# Display.net
KiCad netlist of a schematic drawn in Altium Designer
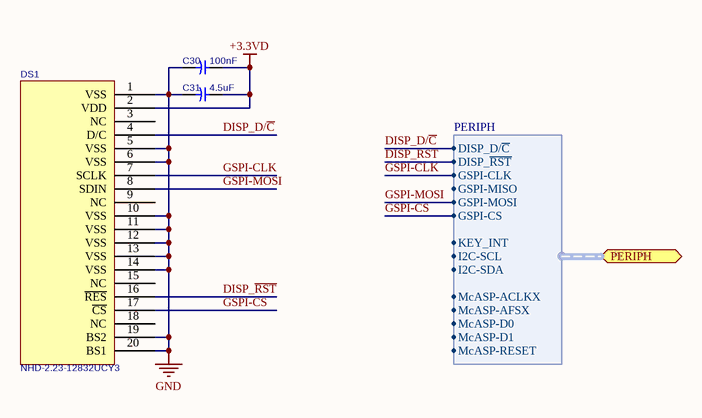
[diagram p0: Display.SchDoc]

(export (version "E")
  (design (tool "Eeschema 10.0.6"))
  (components
    (comp (ref "C30") (value "100nF") (footprint "C_0603A") (libsource (lib "WiFi_3200") (part "C_0603")))
    (comp (ref "C31") (value "4.5uF") (footprint "C_0603A") (libsource (lib "WiFi_3200") (part "C_0603")))
    (comp (ref "DS1")
      (value "NHD-2.23-12832UCY3")
      (footprint "NHD-2.23-12832UCY3_FP")
      (description "OLED DISPLAY")
      (fields (field (name "MANUFACTURER") "Newhaven Display Intl"))
      (libsource (lib "WiFi_3200") (part "NHD-2.23-12832UCY3"))
    )
  )
  (nets
    (net (code "2") (name "+3.3VD") (class "Default")
      (node (ref "C30") (pin "1") (pinfunction "1_1") (pintype "passive"))
      (node (ref "C31") (pin "1") (pinfunction "1_1") (pintype "passive"))
      (node (ref "DS1") (pin "2") (pinfunction "VDD_2") (pintype "passive"))
    )
    (net (code "3") (name "/DISP_D{slash}~{C}") (class "Default")
      (node (ref "DS1") (pin "4") (pinfunction "D/C_4") (pintype "passive"))
    )
    (net (code "4") (name "/DISP_~{RST}") (class "Default")
      (node (ref "DS1") (pin "16") (pinfunction "~{RES}_16") (pintype "passive"))
    )
    (net (code "5") (name "/GSPI-CLK") (class "Default")
      (node (ref "DS1") (pin "7") (pinfunction "SCLK_7") (pintype "passive"))
    )
    (net (code "6") (name "/GSPI-CS") (class "Default")
      (node (ref "DS1") (pin "17") (pinfunction "~{CS}_17") (pintype "passive"))
    )
    (net (code "7") (name "/GSPI-MOSI") (class "Default")
      (node (ref "DS1") (pin "8") (pinfunction "SDIN_8") (pintype "passive"))
    )
    (net (code "9") (name "GND") (class "Default")
      (node (ref "C30") (pin "2") (pinfunction "2_2") (pintype "passive"))
      (node (ref "C31") (pin "2") (pinfunction "2_2") (pintype "passive"))
      (node (ref "DS1") (pin "1") (pinfunction "VSS_1") (pintype "passive"))
      (node (ref "DS1") (pin "10") (pinfunction "VSS_10") (pintype "passive"))
      (node (ref "DS1") (pin "11") (pinfunction "VSS_11") (pintype "passive"))
      (node (ref "DS1") (pin "12") (pinfunction "VSS_12") (pintype "passive"))
      (node (ref "DS1") (pin "13") (pinfunction "VSS_13") (pintype "passive"))
      (node (ref "DS1") (pin "14") (pinfunction "VSS_14") (pintype "passive"))
      (node (ref "DS1") (pin "19") (pinfunction "BS2_19") (pintype "passive"))
      (node (ref "DS1") (pin "20") (pinfunction "BS1_20") (pintype "passive"))
      (node (ref "DS1") (pin "5") (pinfunction "VSS_5") (pintype "passive"))
      (node (ref "DS1") (pin "6") (pinfunction "VSS_6") (pintype "passive"))
    )
    (net (code "10") (name "unconnected-(DS1-NC-Pad3)") (class "Default")
      (node (ref "DS1") (pin "3") (pinfunction "NC_3") (pintype "passive"))
    )
    (net (code "11") (name "unconnected-(DS1-NC-Pad9)") (class "Default")
      (node (ref "DS1") (pin "9") (pinfunction "NC_9") (pintype "passive"))
    )
    (net (code "12") (name "unconnected-(DS1-NC-Pad15)") (class "Default")
      (node (ref "DS1") (pin "15") (pinfunction "NC_15") (pintype "passive"))
    )
    (net (code "13") (name "unconnected-(DS1-NC-Pad18)") (class "Default")
      (node (ref "DS1") (pin "18") (pinfunction "NC_18") (pintype "passive"))
    )
  )
)
